# ECNG3020_Schematic.net
KiCad netlist of a schematic drawn in EAGLE
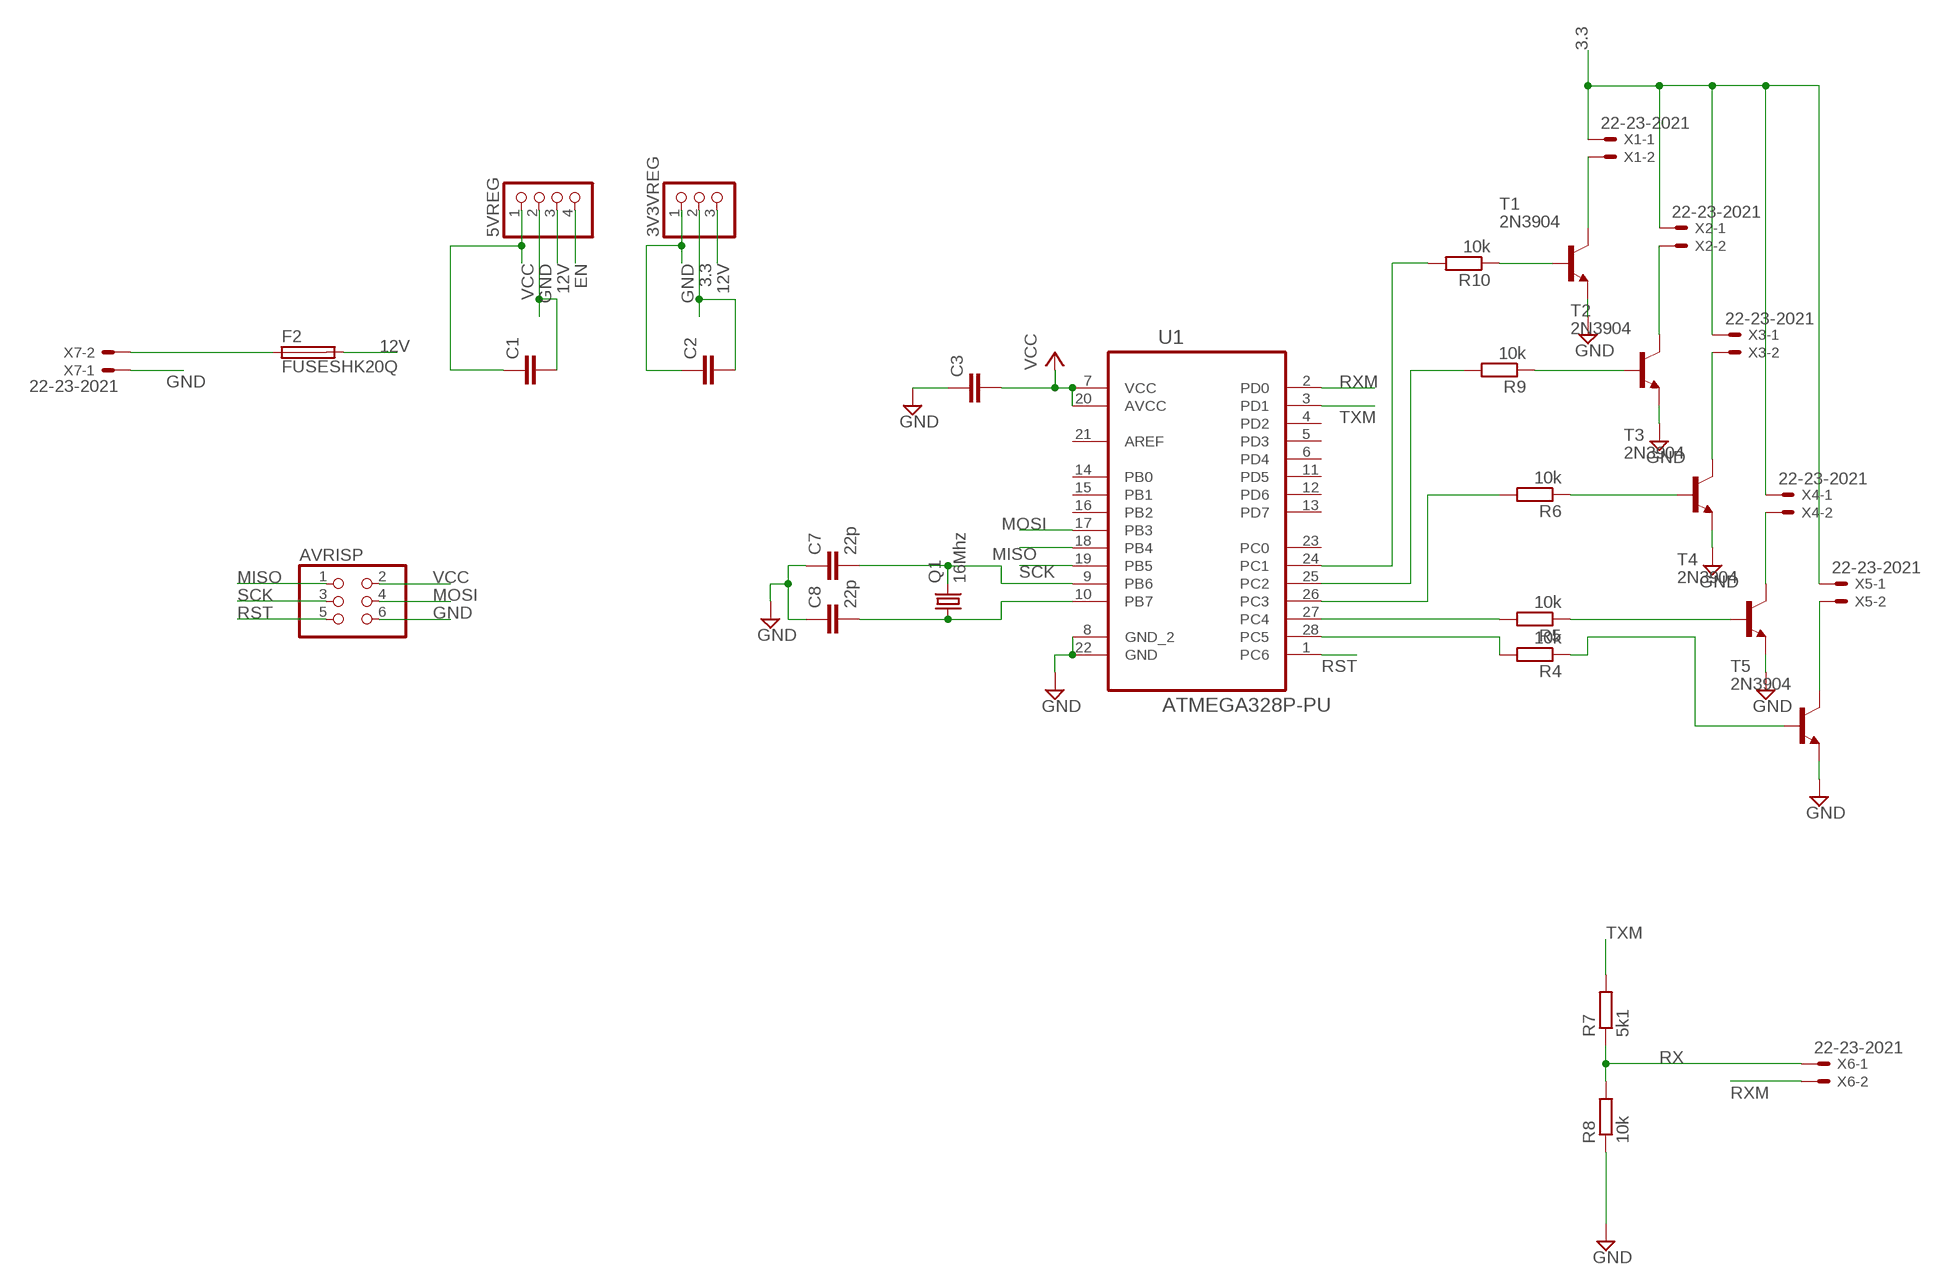
[diagram p0: schematic, sheet 1]

(export (version "E")
  (design (tool "Eeschema 10.0.6"))
  (components
    (comp (ref "3V3VREG")
      (value "PINHD-1X3M")
      (footprint "eagle-import:1X03M")
      (libsource (lib "eagle-import") (part "PINHD-1X3M"))
    )
    (comp (ref "5VREG")
      (value "PINHD-1X4M")
      (footprint "eagle-import:1X04M")
      (libsource (lib "eagle-import") (part "PINHD-1X4M"))
    )
    (comp (ref "AVRISP")
      (value "PINHD-2X3")
      (footprint "eagle-import:2X03")
      (libsource (lib "eagle-import") (part "PINHD-2X3"))
    )
    (comp (ref "C1")
      (value "C2,5-3")
      (footprint "eagle-import:C2.5-3")
      (libsource (lib "eagle-import") (part "C2,5-3"))
    )
    (comp (ref "C2")
      (value "C2,5-3")
      (footprint "eagle-import:C2.5-3")
      (libsource (lib "eagle-import") (part "C2,5-3"))
    )
    (comp (ref "C3")
      (value "C2,5-3")
      (footprint "eagle-import:C2.5-3")
      (libsource (lib "eagle-import") (part "C2,5-3"))
    )
    (comp (ref "C7")
      (value "22p")
      (footprint "eagle-import:C050-024X044")
      (libsource (lib "eagle-import") (part "C-EU050-024X044"))
    )
    (comp (ref "C8")
      (value "22p")
      (footprint "eagle-import:C050-024X044")
      (libsource (lib "eagle-import") (part "C-EU050-024X044"))
    )
    (comp (ref "F2")
      (value "FUSESHK20Q")
      (footprint "eagle-import:SHK20Q")
      (libsource (lib "eagle-import") (part "FUSESHK20Q"))
    )
    (comp (ref "Q1")
      (value "16Mhz")
      (footprint "eagle-import:HC49_S")
      (libsource (lib "eagle-import") (part "CRYSTALHC49S"))
    )
    (comp (ref "R4")
      (value "10k")
      (footprint "eagle-import:0207_10")
      (libsource (lib "eagle-import") (part "R-EU_0207/10"))
    )
    (comp (ref "R5")
      (value "10k")
      (footprint "eagle-import:0207_10")
      (libsource (lib "eagle-import") (part "R-EU_0207/10"))
    )
    (comp (ref "R6")
      (value "10k")
      (footprint "eagle-import:0207_10")
      (libsource (lib "eagle-import") (part "R-EU_0207/10"))
    )
    (comp (ref "R7")
      (value "5k1")
      (footprint "eagle-import:0207_10")
      (libsource (lib "eagle-import") (part "R-EU_0207/10"))
    )
    (comp (ref "R8")
      (value "10k")
      (footprint "eagle-import:0207_10")
      (libsource (lib "eagle-import") (part "R-EU_0207/10"))
    )
    (comp (ref "R9")
      (value "10k")
      (footprint "eagle-import:0207_10")
      (libsource (lib "eagle-import") (part "R-EU_0207/10"))
    )
    (comp (ref "R10")
      (value "10k")
      (footprint "eagle-import:0207_10")
      (libsource (lib "eagle-import") (part "R-EU_0207/10"))
    )
    (comp (ref "T1")
      (value "2N3904")
      (footprint "eagle-import:TO92")
      (libsource (lib "eagle-import") (part "2N3904"))
    )
    (comp (ref "T2")
      (value "2N3904")
      (footprint "eagle-import:TO92")
      (libsource (lib "eagle-import") (part "2N3904"))
    )
    (comp (ref "T3")
      (value "2N3904")
      (footprint "eagle-import:TO92")
      (libsource (lib "eagle-import") (part "2N3904"))
    )
    (comp (ref "T4")
      (value "2N3904")
      (footprint "eagle-import:TO92")
      (libsource (lib "eagle-import") (part "2N3904"))
    )
    (comp (ref "T5")
      (value "2N3904")
      (footprint "eagle-import:TO92")
      (libsource (lib "eagle-import") (part "2N3904"))
    )
    (comp (ref "U1")
      (value "ATMEGA328P-PU")
      (footprint "eagle-import:DIP254P762X457-28")
      (fields (field (name "MF") "Microchip"))
      (libsource (lib "eagle-import") (part "ATMEGA328P-PU"))
    )
    (comp (ref "X1")
      (value "22-23-2021")
      (footprint "eagle-import:22-23-2021")
      (fields (field (name "MF") "MOLEX"))
      (libsource (lib "eagle-import") (part "22-23-2021"))
    )
    (comp (ref "X2")
      (value "22-23-2021")
      (footprint "eagle-import:22-23-2021")
      (fields (field (name "MF") "MOLEX"))
      (libsource (lib "eagle-import") (part "22-23-2021"))
    )
    (comp (ref "X3")
      (value "22-23-2021")
      (footprint "eagle-import:22-23-2021")
      (fields (field (name "MF") "MOLEX"))
      (libsource (lib "eagle-import") (part "22-23-2021"))
    )
    (comp (ref "X4")
      (value "22-23-2021")
      (footprint "eagle-import:22-23-2021")
      (fields (field (name "MF") "MOLEX"))
      (libsource (lib "eagle-import") (part "22-23-2021"))
    )
    (comp (ref "X5")
      (value "22-23-2021")
      (footprint "eagle-import:22-23-2021")
      (fields (field (name "MF") "MOLEX"))
      (libsource (lib "eagle-import") (part "22-23-2021"))
    )
    (comp (ref "X6")
      (value "22-23-2021")
      (footprint "eagle-import:22-23-2021")
      (fields (field (name "MF") "MOLEX"))
      (libsource (lib "eagle-import") (part "22-23-2021"))
    )
    (comp (ref "X7")
      (value "22-23-2021")
      (footprint "eagle-import:22-23-2021")
      (fields (field (name "MF") "MOLEX"))
      (libsource (lib "eagle-import") (part "22-23-2021"))
    )
  )
  (nets
    (net (code "1") (name "/3.3") (class "Default")
      (node (ref "3V3VREG") (pin "2") (pinfunction "2_2") (pintype "passive"))
      (node (ref "C2") (pin "2") (pinfunction "2_2") (pintype "passive"))
      (node (ref "X1") (pin "1") (pinfunction "S_1") (pintype "passive"))
      (node (ref "X2") (pin "1") (pinfunction "S_1") (pintype "passive"))
      (node (ref "X3") (pin "1") (pinfunction "S_1") (pintype "passive"))
      (node (ref "X4") (pin "1") (pinfunction "S_1") (pintype "passive"))
      (node (ref "X5") (pin "1") (pinfunction "S_1") (pintype "passive"))
    )
    (net (code "2") (name "/12V") (class "Default")
      (node (ref "3V3VREG") (pin "3") (pinfunction "3_3") (pintype "passive"))
      (node (ref "5VREG") (pin "3") (pinfunction "3_3") (pintype "passive"))
      (node (ref "F2") (pin "2A") (pinfunction "2_2A") (pintype "passive"))
    )
    (net (code "3") (name "/EN") (class "Default")
      (node (ref "5VREG") (pin "4") (pinfunction "4_4") (pintype "passive"))
    )
    (net (code "4") (name "/MISO") (class "Default")
      (node (ref "AVRISP") (pin "1") (pinfunction "1_1") (pintype "passive"))
      (node (ref "U1") (pin "18") (pinfunction "PB4_18") (pintype "bidirectional"))
    )
    (net (code "5") (name "/MOSI") (class "Default")
      (node (ref "AVRISP") (pin "4") (pinfunction "4_4") (pintype "passive"))
      (node (ref "U1") (pin "17") (pinfunction "PB3_17") (pintype "bidirectional"))
    )
    (net (code "6") (name "/RST") (class "Default")
      (node (ref "AVRISP") (pin "5") (pinfunction "5_5") (pintype "passive"))
      (node (ref "U1") (pin "1") (pinfunction "PC6_1") (pintype "bidirectional"))
    )
    (net (code "7") (name "/RX") (class "Default")
      (node (ref "R7") (pin "1") (pinfunction "1_1") (pintype "passive"))
      (node (ref "R8") (pin "2") (pinfunction "2_2") (pintype "passive"))
      (node (ref "X6") (pin "1") (pinfunction "S_1") (pintype "passive"))
    )
    (net (code "8") (name "/RXM") (class "Default")
      (node (ref "U1") (pin "2") (pinfunction "PD0_2") (pintype "bidirectional"))
      (node (ref "X6") (pin "2") (pinfunction "S_2") (pintype "passive"))
    )
    (net (code "9") (name "/SCK") (class "Default")
      (node (ref "AVRISP") (pin "3") (pinfunction "3_3") (pintype "passive"))
      (node (ref "U1") (pin "19") (pinfunction "PB5_19") (pintype "bidirectional"))
    )
    (net (code "10") (name "/TXM") (class "Default")
      (node (ref "R7") (pin "2") (pinfunction "2_2") (pintype "passive"))
      (node (ref "U1") (pin "3") (pinfunction "PD1_3") (pintype "bidirectional"))
    )
    (net (code "11") (name "GND") (class "Default")
      (node (ref "3V3VREG") (pin "1") (pinfunction "1_1") (pintype "passive"))
      (node (ref "5VREG") (pin "2") (pinfunction "2_2") (pintype "passive"))
      (node (ref "AVRISP") (pin "6") (pinfunction "6_6") (pintype "passive"))
      (node (ref "C1") (pin "2") (pinfunction "2_2") (pintype "passive"))
      (node (ref "C2") (pin "1") (pinfunction "1_1") (pintype "passive"))
      (node (ref "C3") (pin "1") (pinfunction "1_1") (pintype "passive"))
      (node (ref "C7") (pin "1") (pinfunction "1_1") (pintype "passive"))
      (node (ref "C8") (pin "1") (pinfunction "1_1") (pintype "passive"))
      (node (ref "R8") (pin "1") (pinfunction "1_1") (pintype "passive"))
      (node (ref "T1") (pin "3") (pinfunction "E_3") (pintype "passive"))
      (node (ref "T2") (pin "3") (pinfunction "E_3") (pintype "passive"))
      (node (ref "T3") (pin "3") (pinfunction "E_3") (pintype "passive"))
      (node (ref "T4") (pin "3") (pinfunction "E_3") (pintype "passive"))
      (node (ref "T5") (pin "3") (pinfunction "E_3") (pintype "passive"))
      (node (ref "U1") (pin "22") (pinfunction "GND_22") (pintype "passive"))
      (node (ref "U1") (pin "8") (pinfunction "GND_2_8") (pintype "passive"))
      (node (ref "X7") (pin "1") (pinfunction "S_1") (pintype "passive"))
    )
    (net (code "12") (name "Net-(F2-1)") (class "Default")
      (node (ref "F2") (pin "1A") (pinfunction "1_1A") (pintype "passive"))
      (node (ref "X7") (pin "2") (pinfunction "S_2") (pintype "passive"))
    )
    (net (code "13") (name "Net-(T1-B)") (class "Default")
      (node (ref "R10") (pin "1") (pinfunction "1_1") (pintype "passive"))
      (node (ref "T1") (pin "2") (pinfunction "B_2") (pintype "passive"))
    )
    (net (code "14") (name "Net-(T1-C)") (class "Default")
      (node (ref "T1") (pin "1") (pinfunction "C_1") (pintype "passive"))
      (node (ref "X1") (pin "2") (pinfunction "S_2") (pintype "passive"))
    )
    (net (code "15") (name "Net-(T2-B)") (class "Default")
      (node (ref "R9") (pin "1") (pinfunction "1_1") (pintype "passive"))
      (node (ref "T2") (pin "2") (pinfunction "B_2") (pintype "passive"))
    )
    (net (code "16") (name "Net-(T2-C)") (class "Default")
      (node (ref "T2") (pin "1") (pinfunction "C_1") (pintype "passive"))
      (node (ref "X2") (pin "2") (pinfunction "S_2") (pintype "passive"))
    )
    (net (code "17") (name "Net-(T3-B)") (class "Default")
      (node (ref "R6") (pin "1") (pinfunction "1_1") (pintype "passive"))
      (node (ref "T3") (pin "2") (pinfunction "B_2") (pintype "passive"))
    )
    (net (code "18") (name "Net-(T3-C)") (class "Default")
      (node (ref "T3") (pin "1") (pinfunction "C_1") (pintype "passive"))
      (node (ref "X3") (pin "2") (pinfunction "S_2") (pintype "passive"))
    )
    (net (code "19") (name "Net-(T4-B)") (class "Default")
      (node (ref "R5") (pin "1") (pinfunction "1_1") (pintype "passive"))
      (node (ref "T4") (pin "2") (pinfunction "B_2") (pintype "passive"))
    )
    (net (code "20") (name "Net-(T4-C)") (class "Default")
      (node (ref "T4") (pin "1") (pinfunction "C_1") (pintype "passive"))
      (node (ref "X4") (pin "2") (pinfunction "S_2") (pintype "passive"))
    )
    (net (code "21") (name "Net-(T5-B)") (class "Default")
      (node (ref "R4") (pin "1") (pinfunction "1_1") (pintype "passive"))
      (node (ref "T5") (pin "2") (pinfunction "B_2") (pintype "passive"))
    )
    (net (code "22") (name "Net-(T5-C)") (class "Default")
      (node (ref "T5") (pin "1") (pinfunction "C_1") (pintype "passive"))
      (node (ref "X5") (pin "2") (pinfunction "S_2") (pintype "passive"))
    )
    (net (code "23") (name "Net-(U1-PB6)") (class "Default")
      (node (ref "C7") (pin "2") (pinfunction "2_2") (pintype "passive"))
      (node (ref "Q1") (pin "2") (pinfunction "2_2") (pintype "passive"))
      (node (ref "U1") (pin "9") (pinfunction "PB6_9") (pintype "bidirectional"))
    )
    (net (code "24") (name "Net-(U1-PB7)") (class "Default")
      (node (ref "C8") (pin "2") (pinfunction "2_2") (pintype "passive"))
      (node (ref "Q1") (pin "1") (pinfunction "1_1") (pintype "passive"))
      (node (ref "U1") (pin "10") (pinfunction "PB7_10") (pintype "bidirectional"))
    )
    (net (code "25") (name "Net-(U1-PC1)") (class "Default")
      (node (ref "R10") (pin "2") (pinfunction "2_2") (pintype "passive"))
      (node (ref "U1") (pin "24") (pinfunction "PC1_24") (pintype "bidirectional"))
    )
    (net (code "26") (name "Net-(U1-PC2)") (class "Default")
      (node (ref "R9") (pin "2") (pinfunction "2_2") (pintype "passive"))
      (node (ref "U1") (pin "25") (pinfunction "PC2_25") (pintype "bidirectional"))
    )
    (net (code "27") (name "Net-(U1-PC3)") (class "Default")
      (node (ref "R6") (pin "2") (pinfunction "2_2") (pintype "passive"))
      (node (ref "U1") (pin "26") (pinfunction "PC3_26") (pintype "bidirectional"))
    )
    (net (code "28") (name "Net-(U1-PC4)") (class "Default")
      (node (ref "R5") (pin "2") (pinfunction "2_2") (pintype "passive"))
      (node (ref "U1") (pin "27") (pinfunction "PC4_27") (pintype "bidirectional"))
    )
    (net (code "29") (name "Net-(U1-PC5)") (class "Default")
      (node (ref "R4") (pin "2") (pinfunction "2_2") (pintype "passive"))
      (node (ref "U1") (pin "28") (pinfunction "PC5_28") (pintype "bidirectional"))
    )
    (net (code "30") (name "VCC") (class "Default")
      (node (ref "5VREG") (pin "1") (pinfunction "1_1") (pintype "passive"))
      (node (ref "AVRISP") (pin "2") (pinfunction "2_2") (pintype "passive"))
      (node (ref "C1") (pin "1") (pinfunction "1_1") (pintype "passive"))
      (node (ref "C3") (pin "2") (pinfunction "2_2") (pintype "passive"))
      (node (ref "U1") (pin "20") (pinfunction "AVCC_20") (pintype "power_in"))
      (node (ref "U1") (pin "7") (pinfunction "VCC_7") (pintype "power_in"))
    )
    (net (code "31") (name "unconnected-(U1-AREF-Pad21)") (class "Default")
      (node (ref "U1") (pin "21") (pinfunction "AREF_21") (pintype "input"))
    )
    (net (code "32") (name "unconnected-(U1-PB0-Pad14)") (class "Default")
      (node (ref "U1") (pin "14") (pinfunction "PB0_14") (pintype "bidirectional"))
    )
    (net (code "33") (name "unconnected-(U1-PB1-Pad15)") (class "Default")
      (node (ref "U1") (pin "15") (pinfunction "PB1_15") (pintype "bidirectional"))
    )
    (net (code "34") (name "unconnected-(U1-PB2-Pad16)") (class "Default")
      (node (ref "U1") (pin "16") (pinfunction "PB2_16") (pintype "bidirectional"))
    )
    (net (code "35") (name "unconnected-(U1-PC0-Pad23)") (class "Default")
      (node (ref "U1") (pin "23") (pinfunction "PC0_23") (pintype "bidirectional"))
    )
    (net (code "36") (name "unconnected-(U1-PD2-Pad4)") (class "Default")
      (node (ref "U1") (pin "4") (pinfunction "PD2_4") (pintype "bidirectional"))
    )
    (net (code "37") (name "unconnected-(U1-PD3-Pad5)") (class "Default")
      (node (ref "U1") (pin "5") (pinfunction "PD3_5") (pintype "bidirectional"))
    )
    (net (code "38") (name "unconnected-(U1-PD4-Pad6)") (class "Default")
      (node (ref "U1") (pin "6") (pinfunction "PD4_6") (pintype "bidirectional"))
    )
    (net (code "39") (name "unconnected-(U1-PD5-Pad11)") (class "Default")
      (node (ref "U1") (pin "11") (pinfunction "PD5_11") (pintype "bidirectional"))
    )
    (net (code "40") (name "unconnected-(U1-PD6-Pad12)") (class "Default")
      (node (ref "U1") (pin "12") (pinfunction "PD6_12") (pintype "bidirectional"))
    )
    (net (code "41") (name "unconnected-(U1-PD7-Pad13)") (class "Default")
      (node (ref "U1") (pin "13") (pinfunction "PD7_13") (pintype "bidirectional"))
    )
  )
)
